# DSO_CPLD.net
KiCad netlist of a schematic drawn in Altium Designer
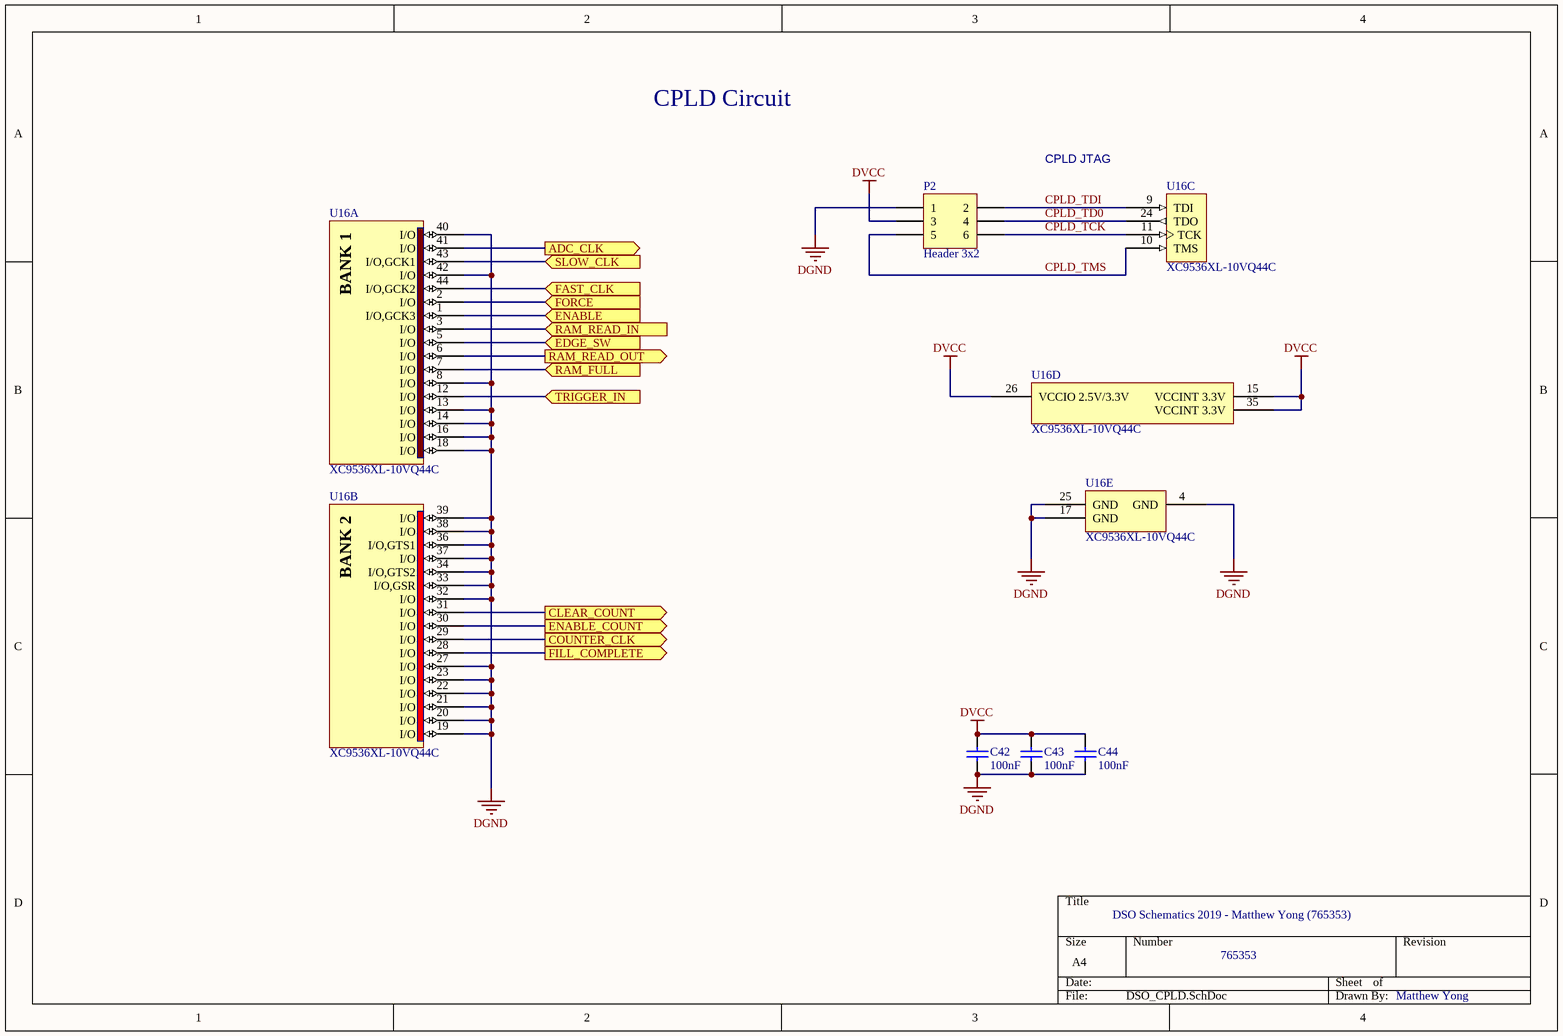
[diagram p0: DSO_CPLD.SchDoc]

(export (version "E")
  (design (tool "Eeschema 10.0.6"))
  (components
    (comp (ref "C42")
      (value "100nF")
      (footprint "0805C")
      (description "Capacitor")
      (fields (field (name "REVIEWED BY") "RM - 2018/08/05"))
      (libsource (lib "DSO") (part "C"))
    )
    (comp (ref "C43")
      (value "100nF")
      (footprint "0805C")
      (description "Capacitor")
      (fields (field (name "REVIEWED BY") "RM - 2018/08/05"))
      (libsource (lib "DSO") (part "C"))
    )
    (comp (ref "C44")
      (value "100nF")
      (footprint "0805C")
      (description "Capacitor")
      (fields (field (name "REVIEWED BY") "RM - 2018/08/05"))
      (libsource (lib "DSO") (part "C"))
    )
    (comp (ref "P2")
      (value "Header 3x2")
      (footprint "HDR3x2")
      (description "Header, 5-Pin")
      (fields (field (name "REVIEWED BY") "RM - 2018/08/05"))
      (libsource (lib "DSO") (part "Header 3x2"))
    )
    (comp (ref "U16")
      (value "XC9536XL-10VQ44C")
      (footprint "VQ44_L")
      (fields (field (name "REVIEWED BY") "RM - 2018/08/05"))
      (libsource (lib "DSO") (part "XC9536XL-10VQG44C"))
    )
  )
  (nets
    (net (code "1") (name "/ADC_CLK") (class "Default")
      (node (ref "U16") (pin "41") (pinfunction "I/O_41") (pintype "bidirectional"))
    )
    (net (code "2") (name "/CLEAR_COUNT") (class "Default")
      (node (ref "U16") (pin "31") (pinfunction "I/O_31") (pintype "bidirectional"))
    )
    (net (code "3") (name "/COUNTER_CLK") (class "Default")
      (node (ref "U16") (pin "29") (pinfunction "I/O_29") (pintype "bidirectional"))
    )
    (net (code "4") (name "/CPLD_TCK") (class "Default")
      (node (ref "P2") (pin "6") (pinfunction "6_6") (pintype "passive"))
      (node (ref "U16") (pin "11") (pinfunction "TCK_11") (pintype "input"))
    )
    (net (code "5") (name "/CPLD_TD0") (class "Default")
      (node (ref "P2") (pin "4") (pinfunction "4_4") (pintype "passive"))
      (node (ref "U16") (pin "24") (pinfunction "TDO_24") (pintype "output"))
    )
    (net (code "6") (name "/CPLD_TDI") (class "Default")
      (node (ref "P2") (pin "2") (pinfunction "2_2") (pintype "passive"))
      (node (ref "U16") (pin "9") (pinfunction "TDI_9") (pintype "input"))
    )
    (net (code "7") (name "/CPLD_TMS") (class "Default")
      (node (ref "P2") (pin "5") (pinfunction "5_5") (pintype "passive"))
      (node (ref "U16") (pin "10") (pinfunction "TMS_10") (pintype "input"))
    )
    (net (code "8") (name "/EDGE_SW") (class "Default")
      (node (ref "U16") (pin "5") (pinfunction "I/O_5") (pintype "bidirectional"))
    )
    (net (code "9") (name "/ENABLE") (class "Default")
      (node (ref "U16") (pin "1") (pinfunction "I/O,GCK3_1") (pintype "bidirectional"))
    )
    (net (code "10") (name "/ENABLE_COUNT") (class "Default")
      (node (ref "U16") (pin "30") (pinfunction "I/O_30") (pintype "bidirectional"))
    )
    (net (code "11") (name "/FAST_CLK") (class "Default")
      (node (ref "U16") (pin "44") (pinfunction "I/O,GCK2_44") (pintype "bidirectional"))
    )
    (net (code "12") (name "/FILL_COMPLETE") (class "Default")
      (node (ref "U16") (pin "28") (pinfunction "I/O_28") (pintype "bidirectional"))
    )
    (net (code "13") (name "/FORCE") (class "Default")
      (node (ref "U16") (pin "2") (pinfunction "I/O_2") (pintype "bidirectional"))
    )
    (net (code "14") (name "/RAM_FULL") (class "Default")
      (node (ref "U16") (pin "7") (pinfunction "I/O_7") (pintype "bidirectional"))
    )
    (net (code "15") (name "/RAM_READ_IN") (class "Default")
      (node (ref "U16") (pin "3") (pinfunction "I/O_3") (pintype "bidirectional"))
    )
    (net (code "16") (name "/RAM_READ_OUT") (class "Default")
      (node (ref "U16") (pin "6") (pinfunction "I/O_6") (pintype "bidirectional"))
    )
    (net (code "17") (name "/SLOW_CLK") (class "Default")
      (node (ref "U16") (pin "43") (pinfunction "I/O,GCK1_43") (pintype "bidirectional"))
    )
    (net (code "18") (name "/TRIGGER_IN") (class "Default")
      (node (ref "U16") (pin "12") (pinfunction "I/O_12") (pintype "bidirectional"))
    )
    (net (code "19") (name "DGND") (class "Default")
      (node (ref "C42") (pin "2") (pinfunction "2_2") (pintype "passive"))
      (node (ref "C43") (pin "2") (pinfunction "2_2") (pintype "passive"))
      (node (ref "C44") (pin "2") (pinfunction "2_2") (pintype "passive"))
      (node (ref "P2") (pin "1") (pinfunction "1_1") (pintype "passive"))
      (node (ref "U16") (pin "13") (pinfunction "I/O_13") (pintype "bidirectional"))
      (node (ref "U16") (pin "14") (pinfunction "I/O_14") (pintype "bidirectional"))
      (node (ref "U16") (pin "16") (pinfunction "I/O_16") (pintype "bidirectional"))
      (node (ref "U16") (pin "17") (pinfunction "GND_17") (pintype "power_in"))
      (node (ref "U16") (pin "18") (pinfunction "I/O_18") (pintype "bidirectional"))
      (node (ref "U16") (pin "19") (pinfunction "I/O_19") (pintype "bidirectional"))
      (node (ref "U16") (pin "20") (pinfunction "I/O_20") (pintype "bidirectional"))
      (node (ref "U16") (pin "21") (pinfunction "I/O_21") (pintype "bidirectional"))
      (node (ref "U16") (pin "22") (pinfunction "I/O_22") (pintype "bidirectional"))
      (node (ref "U16") (pin "23") (pinfunction "I/O_23") (pintype "bidirectional"))
      (node (ref "U16") (pin "25") (pinfunction "GND_25") (pintype "power_in"))
      (node (ref "U16") (pin "27") (pinfunction "I/O_27") (pintype "bidirectional"))
      (node (ref "U16") (pin "32") (pinfunction "I/O_32") (pintype "bidirectional"))
      (node (ref "U16") (pin "33") (pinfunction "I/O,GSR_33") (pintype "bidirectional"))
      (node (ref "U16") (pin "34") (pinfunction "I/O,GTS2_34") (pintype "bidirectional"))
      (node (ref "U16") (pin "36") (pinfunction "I/O,GTS1_36") (pintype "bidirectional"))
      (node (ref "U16") (pin "37") (pinfunction "I/O_37") (pintype "bidirectional"))
      (node (ref "U16") (pin "38") (pinfunction "I/O_38") (pintype "bidirectional"))
      (node (ref "U16") (pin "39") (pinfunction "I/O_39") (pintype "bidirectional"))
      (node (ref "U16") (pin "4") (pinfunction "GND_4") (pintype "power_in"))
      (node (ref "U16") (pin "40") (pinfunction "I/O_40") (pintype "bidirectional"))
      (node (ref "U16") (pin "42") (pinfunction "I/O_42") (pintype "bidirectional"))
      (node (ref "U16") (pin "8") (pinfunction "I/O_8") (pintype "bidirectional"))
    )
    (net (code "20") (name "DVCC") (class "Default")
      (node (ref "C42") (pin "1") (pinfunction "1_1") (pintype "passive"))
      (node (ref "C43") (pin "1") (pinfunction "1_1") (pintype "passive"))
      (node (ref "C44") (pin "1") (pinfunction "1_1") (pintype "passive"))
      (node (ref "P2") (pin "3") (pinfunction "3_3") (pintype "passive"))
      (node (ref "U16") (pin "15") (pinfunction "VCCINT_3.3V_15") (pintype "power_in"))
      (node (ref "U16") (pin "26") (pinfunction "VCCIO_2.5V/3.3V_26") (pintype "power_in"))
      (node (ref "U16") (pin "35") (pinfunction "VCCINT_3.3V_35") (pintype "power_in"))
    )
  )
)
